# SCH_MUSICA_2024-05-24.net
KiCad netlist of a schematic drawn in EasyEDA
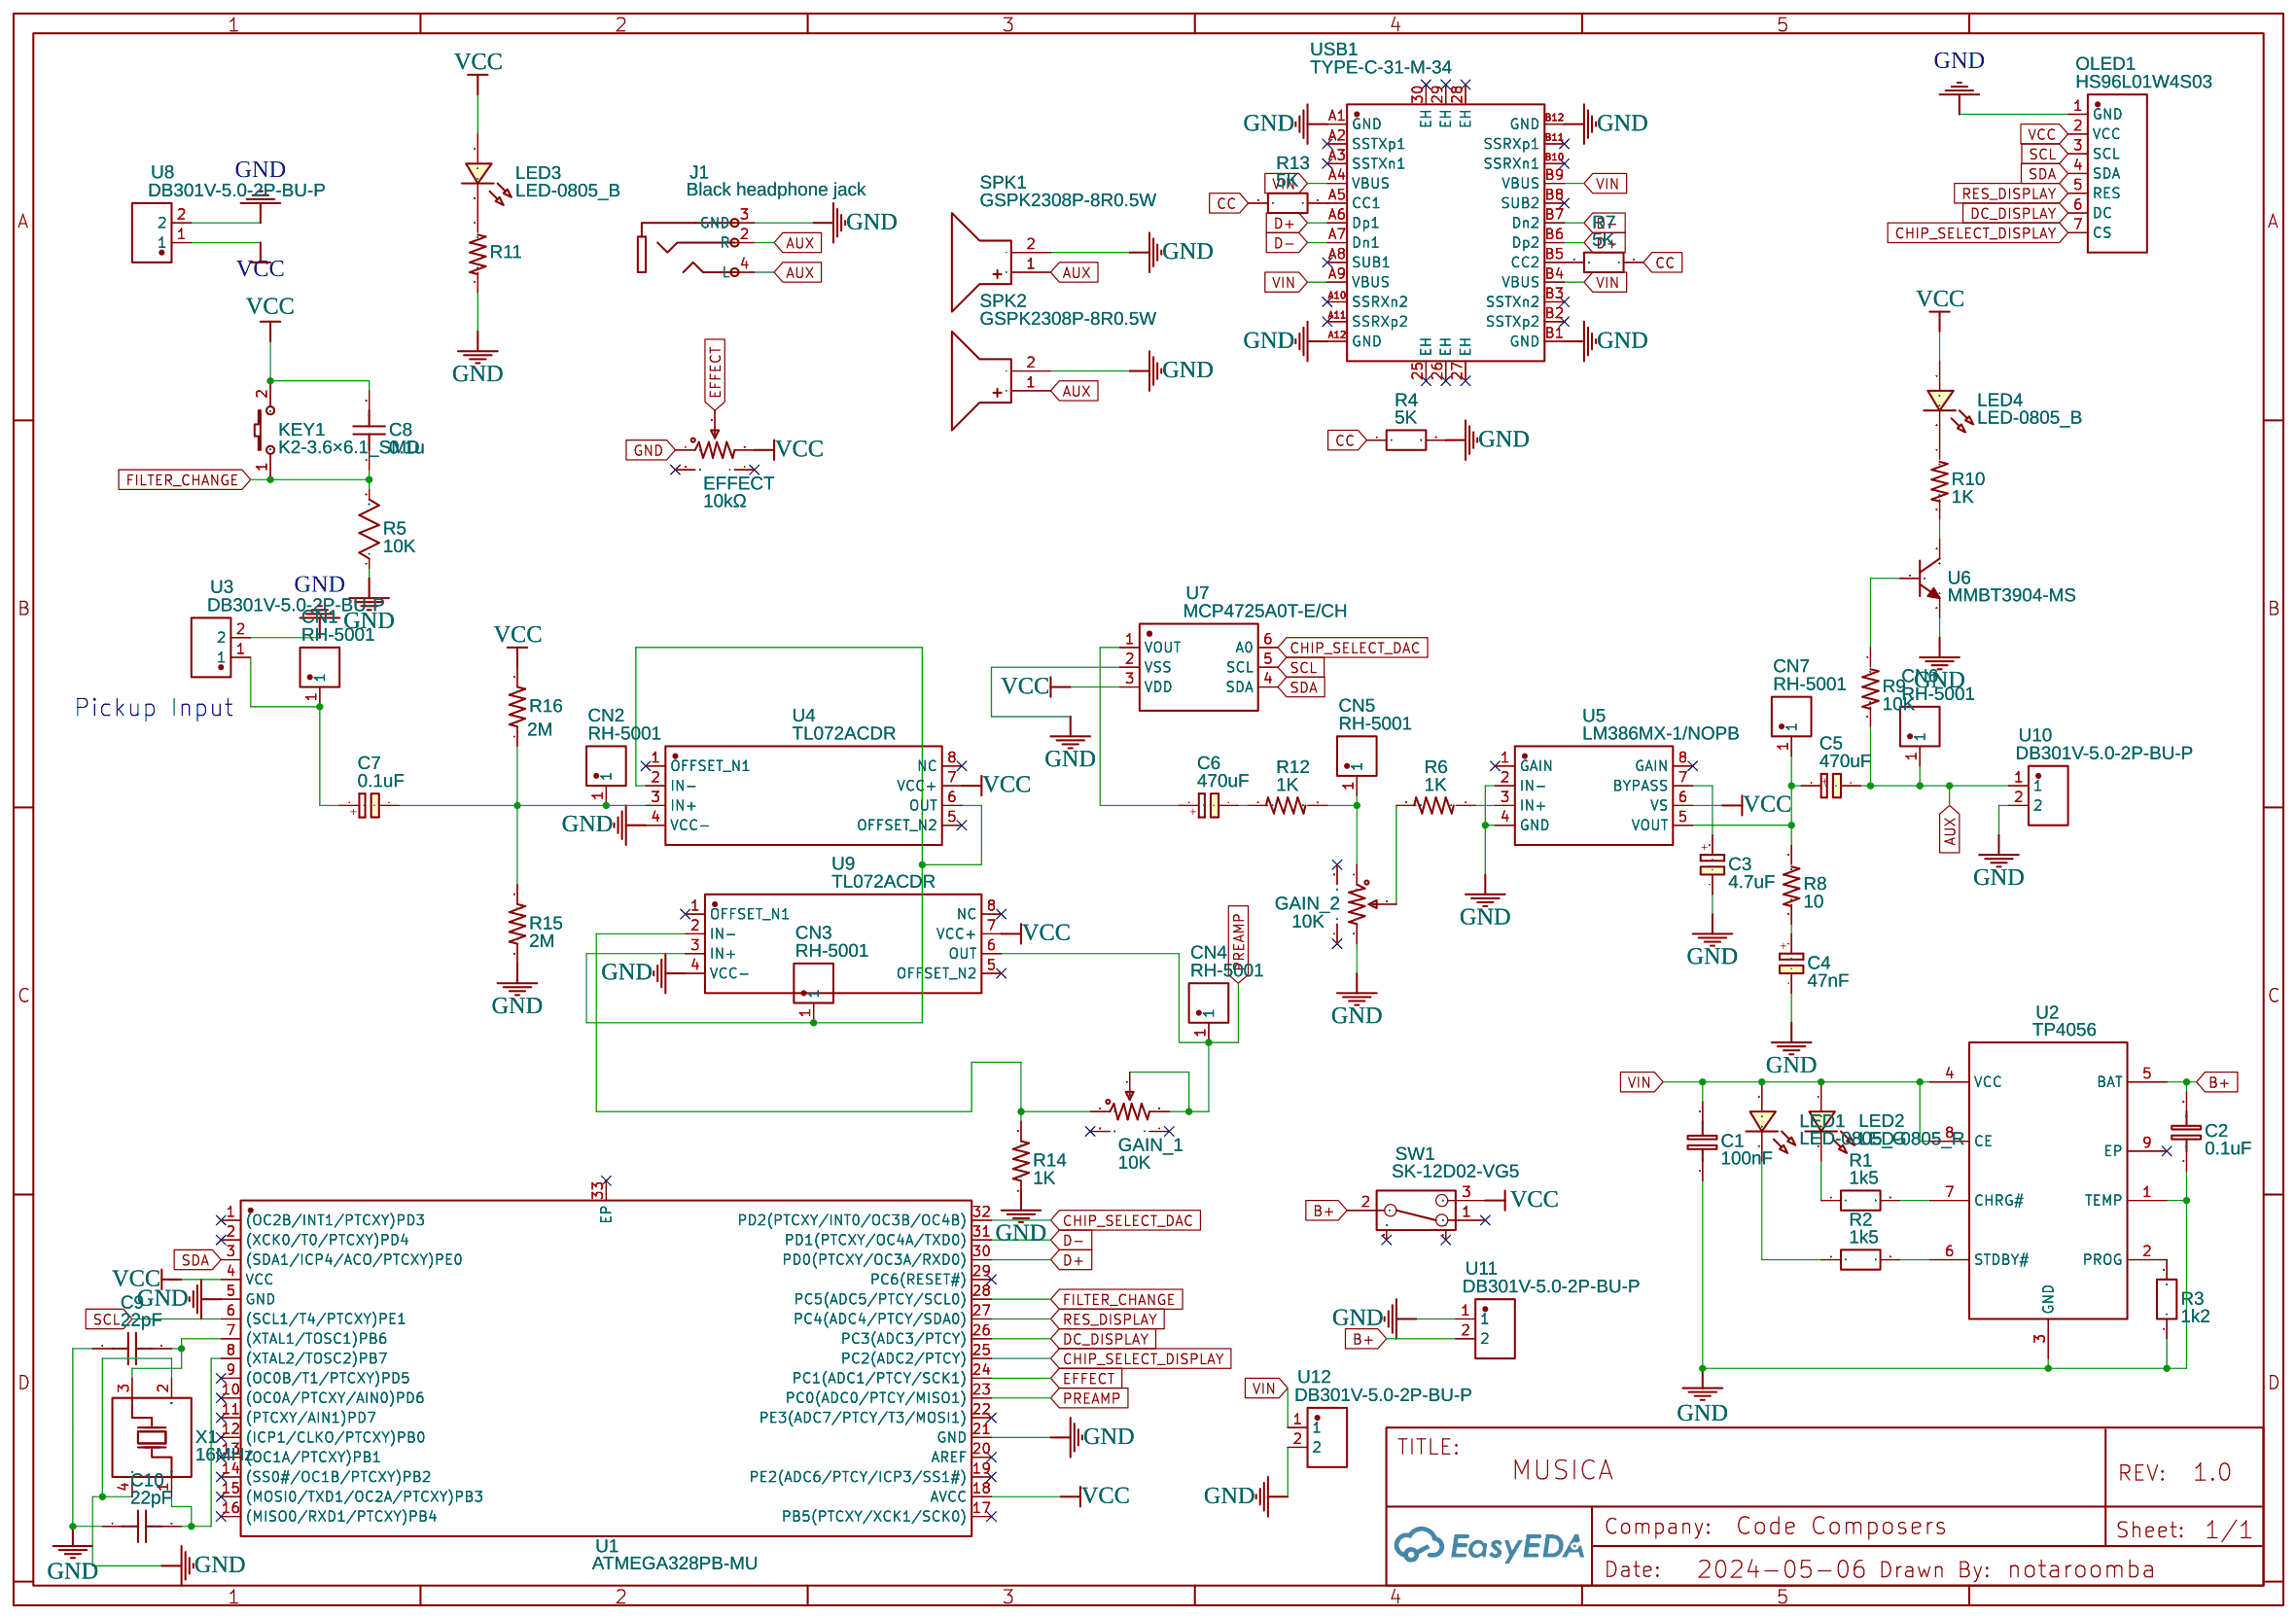
[diagram p0: schematic sheet]

(export (version "E")
  (design (tool "Eeschema 10.0.6"))
  (components
    (comp (ref "C1") (value "100nF") (libsource (lib "") (part "C_0603_EU")))
    (comp (ref "C2") (value "0.1uF") (libsource (lib "") (part "C_0603_EU")))
    (comp (ref "C3") (value "4.7uF") (libsource (lib "") (part "CAPACITOR_POL_S_2")))
    (comp (ref "C4") (value "47nF") (libsource (lib "") (part "CAPACITOR_POL_S_2")))
    (comp (ref "C5") (value "470uF") (libsource (lib "") (part "CAPACITOR_POL_S")))
    (comp (ref "C6") (value "470uF") (libsource (lib "") (part "CAPACITOR_POL_S_1")))
    (comp (ref "C7") (value "0.1uF") (libsource (lib "") (part "CAPACITOR_POL_S_1")))
    (comp (ref "C8") (value "0.1u") (libsource (lib "") (part "C_0603_US")))
    (comp (ref "C9") (value "22pF") (libsource (lib "") (part "C_0603_US_1")))
    (comp (ref "C10") (value "22pF") (libsource (lib "") (part "C_0603_US_1")))
    (comp (ref "CN1")
      (value "RH-5001")
      (fields (field (name "Manufacturer") "荣和"))
      (libsource (lib "") (part "RH-5001"))
    )
    (comp (ref "CN2")
      (value "RH-5001")
      (fields (field (name "Manufacturer") "荣和"))
      (libsource (lib "") (part "RH-5001"))
    )
    (comp (ref "CN3")
      (value "RH-5001")
      (fields (field (name "Manufacturer") "荣和"))
      (libsource (lib "") (part "RH-5001"))
    )
    (comp (ref "CN4")
      (value "RH-5001")
      (fields (field (name "Manufacturer") "荣和"))
      (libsource (lib "") (part "RH-5001"))
    )
    (comp (ref "CN5")
      (value "RH-5001")
      (fields (field (name "Manufacturer") "荣和"))
      (libsource (lib "") (part "RH-5001"))
    )
    (comp (ref "CN6")
      (value "RH-5001")
      (fields (field (name "Manufacturer") "荣和"))
      (libsource (lib "") (part "RH-5001"))
    )
    (comp (ref "CN7")
      (value "RH-5001")
      (fields (field (name "Manufacturer") "荣和"))
      (libsource (lib "") (part "RH-5001"))
    )
    (comp (ref "EFFECT")
      (value "10kΩ")
      (fields
        (field (name "Manufacturer Part") "RK09L114001T")
        (field (name "Manufacturer") "ALPSALPINE(阿尔卑斯阿尔派)")
      )
      (libsource (lib "") (part "RK09L114001T_1"))
    )
    (comp (ref "GAIN_1")
      (value "10K")
      (fields
        (field (name "Manufacturer Part") "RK09L114001T")
        (field (name "Manufacturer") "ALPSALPINE(阿尔卑斯阿尔派)")
      )
      (libsource (lib "") (part "RK09L114001T_2"))
    )
    (comp (ref "GAIN_2")
      (value "10K")
      (fields
        (field (name "Manufacturer Part") "RK09L114001T")
        (field (name "Manufacturer") "ALPSALPINE(阿尔卑斯阿尔派)")
      )
      (libsource (lib "") (part "RK09L114001T"))
    )
    (comp (ref "J1")
      (value "Black headphone jack")
      (fields (field (name "Manufacturer Part") "320B直插") (field (name "Manufacturer") "BOOMELE(博穆精密)"))
      (libsource (lib "") (part "Black headphone jack"))
    )
    (comp (ref "KEY1")
      (value "K2-3.6×6.1_SMD")
      (fields (field (name "Manufacturer Part") "K2-1107ST-A4SW-06"))
      (libsource (lib "") (part "K2-3.6×6.1_SMD"))
    )
    (comp (ref "LED1")
      (value "LED-0805_G")
      (fields (field (name "Manufacturer Part") "NCD0805G1") (field (name "Manufacturer") "国星光电"))
      (libsource (lib "") (part "LED-0805_G"))
    )
    (comp (ref "LED2")
      (value "LED-0805_R")
      (fields
        (field (name "Manufacturer Part") "17-21SURC/S530-A3/TR8")
        (field (name "Manufacturer") "EVERLIGHT(台湾亿光)")
      )
      (libsource (lib "") (part "LED-0805_R"))
    )
    (comp (ref "LED3")
      (value "LED-0805_B")
      (fields (field (name "Manufacturer Part") "D-B080508B1-KS2") (field (name "Manufacturer") "方舟 ARKLED"))
      (libsource (lib "") (part "LED-0805_B"))
    )
    (comp (ref "LED4")
      (value "LED-0805_B")
      (fields (field (name "Manufacturer Part") "D-B080508B1-KS2") (field (name "Manufacturer") "方舟 ARKLED"))
      (libsource (lib "") (part "LED-0805_B"))
    )
    (comp (ref "OLED1")
      (value "HS96L01W4S03")
      (fields (field (name "Manufacturer") "HS(汉昇)"))
      (libsource (lib "") (part "HS96L01W4S03"))
    )
    (comp (ref "R1") (value "1k5") (libsource (lib "") (part "R_0603_EU")))
    (comp (ref "R2") (value "1k5") (libsource (lib "") (part "R_0603_EU")))
    (comp (ref "R3") (value "1k2") (libsource (lib "") (part "R_0603_EU_1")))
    (comp (ref "R4") (value "5K") (libsource (lib "") (part "R_0603_EU")))
    (comp (ref "R5") (value "10K") (libsource (lib "") (part "R_0603_US")))
    (comp (ref "R6") (value "1K") (libsource (lib "") (part "RESISTOR0805-RES_1")))
    (comp (ref "R7") (value "5K") (libsource (lib "") (part "R_0603_EU")))
    (comp (ref "R8") (value "10") (libsource (lib "") (part "RESISTOR0805-RES_2")))
    (comp (ref "R9") (value "10K") (libsource (lib "") (part "RESISTOR0805-RES_2")))
    (comp (ref "R10") (value "1K") (libsource (lib "") (part "RESISTOR0805-RES_2")))
    (comp (ref "R11") (value "1K") (libsource (lib "") (part "RESISTOR0805-RES_2")))
    (comp (ref "R12") (value "1K") (libsource (lib "") (part "RESISTOR0805-RES_1")))
    (comp (ref "R13") (value "5K") (libsource (lib "") (part "R_0603_EU")))
    (comp (ref "R14") (value "1K") (libsource (lib "") (part "RESISTOR0805-RES")))
    (comp (ref "R15") (value "2M") (libsource (lib "") (part "RESISTOR0805-RES")))
    (comp (ref "R16") (value "2M") (libsource (lib "") (part "RESISTOR0805-RES")))
    (comp (ref "SPK1")
      (value "GSPK2308P-8R0.5W")
      (fields (field (name "Manufacturer") "INGHAi(赢海)"))
      (libsource (lib "") (part "GSPK2308P-8R0.5W"))
    )
    (comp (ref "SPK2")
      (value "GSPK2308P-8R0.5W")
      (fields (field (name "Manufacturer") "INGHAi(赢海)"))
      (libsource (lib "") (part "GSPK2308P-8R0.5W"))
    )
    (comp (ref "SW1")
      (value "SK-12D02-VG5")
      (fields (field (name "Manufacturer") "Rectangular Connectors - Contacts"))
      (libsource (lib "") (part "SK-12D02-VG5"))
    )
    (comp (ref "U1")
      (value "ATMEGA328PB-MU")
      (fields (field (name "Manufacturer") "MICROCHIP(美国微芯)"))
      (libsource (lib "") (part "ATMEGA328PB-MU"))
    )
    (comp (ref "U2")
      (value "TP4056")
      (fields
        (field (name "Manufacturer Part") "TP4056-42-ESOP8")
        (field (name "Manufacturer") "TOPPOWER(南京拓微)")
      )
      (libsource (lib "") (part "TP4056"))
    )
    (comp (ref "U3")
      (value "DB301V-5.0-2P-BU-P")
      (fields (field (name "Manufacturer") "DORABO(地博电气)"))
      (libsource (lib "") (part "DB301V-5.0-2P-BU-P_1"))
    )
    (comp (ref "U4")
      (value "TL072ACDR")
      (fields (field (name "Manufacturer") "TI(德州仪器)"))
      (libsource (lib "") (part "TL072ACDR"))
    )
    (comp (ref "U5")
      (value "LM386MX-1/NOPB")
      (fields (field (name "Manufacturer") "TI(德州仪器)"))
      (libsource (lib "") (part "LM386MX-1/NOPB"))
    )
    (comp (ref "U6")
      (value "MMBT3904-MS")
      (fields (field (name "Manufacturer") "MSKSEMI(美森科)"))
      (libsource (lib "") (part "MMBT3904-MS"))
    )
    (comp (ref "U7")
      (value "MCP4725A0T-E/CH")
      (fields (field (name "Manufacturer") "MICROCHIP(美国微芯)"))
      (libsource (lib "") (part "MCP4725A0T-E/CH"))
    )
    (comp (ref "U8")
      (value "DB301V-5.0-2P-BU-P")
      (fields (field (name "Manufacturer") "DORABO(地博电气)"))
      (libsource (lib "") (part "DB301V-5.0-2P-BU-P_1"))
    )
    (comp (ref "U9")
      (value "TL072ACDR")
      (fields (field (name "Manufacturer") "TI(德州仪器)"))
      (libsource (lib "") (part "TL072ACDR"))
    )
    (comp (ref "U10")
      (value "DB301V-5.0-2P-BU-P")
      (fields (field (name "Manufacturer") "DORABO(地博电气)"))
      (libsource (lib "") (part "DB301V-5.0-2P-BU-P"))
    )
    (comp (ref "U11")
      (value "DB301V-5.0-2P-BU-P")
      (fields (field (name "Manufacturer") "DORABO(地博电气)"))
      (libsource (lib "") (part "DB301V-5.0-2P-BU-P"))
    )
    (comp (ref "U12")
      (value "DB301V-5.0-2P-BU-P")
      (fields (field (name "Manufacturer") "DORABO(地博电气)"))
      (libsource (lib "") (part "DB301V-5.0-2P-BU-P"))
    )
    (comp (ref "USB1")
      (value "TYPE-C-31-M-34")
      (fields (field (name "Manufacturer") "韩国韩荣"))
      (libsource (lib "") (part "TYPE-C-31-M-34"))
    )
    (comp (ref "X1")
      (value "16MHz")
      (fields (field (name "Manufacturer Part") "X322516MLB4SI") (field (name "Manufacturer") "YXC(扬兴晶振)"))
      (libsource (lib "") (part "X322516MLB4SI"))
    )
  )
  (nets
    (net (code "1") (name "AUX") (class "Default")
      (node (ref "C5") (pin "-") (pinfunction "-_-") (pintype "unspecified"))
      (node (ref "CN6") (pin "1") (pinfunction "1_1") (pintype "unspecified"))
      (node (ref "J1") (pin "2") (pinfunction "R_2") (pintype "input"))
      (node (ref "J1") (pin "4") (pinfunction "L_4") (pintype "input"))
      (node (ref "R9") (pin "2") (pinfunction "2_2") (pintype "bidirectional"))
      (node (ref "SPK1") (pin "1") (pinfunction "+_1") (pintype "unspecified"))
      (node (ref "SPK2") (pin "1") (pinfunction "+_1") (pintype "unspecified"))
      (node (ref "U10") (pin "1") (pinfunction "1_1") (pintype "unspecified"))
    )
    (net (code "2") (name "B+") (class "Default")
      (node (ref "C2") (pin "2") (pinfunction "2_2") (pintype "unspecified"))
      (node (ref "SW1") (pin "2") (pinfunction "2_2") (pintype "unspecified"))
      (node (ref "U11") (pin "2") (pinfunction "2_2") (pintype "unspecified"))
      (node (ref "U2") (pin "5") (pinfunction "BAT_5") (pintype "unspecified"))
    )
    (net (code "3") (name "CC") (class "Default")
      (node (ref "R13") (pin "1") (pinfunction "1_1") (pintype "unspecified"))
      (node (ref "R4") (pin "1") (pinfunction "1_1") (pintype "unspecified"))
      (node (ref "R7") (pin "2") (pinfunction "2_2") (pintype "unspecified"))
    )
    (net (code "4") (name "CHIP_SELECT_DAC") (class "Default")
      (node (ref "U1") (pin "32") (pinfunction "PD2(PTCXY/INT0/OC3B/OC4B)_32") (pintype "unspecified"))
      (node (ref "U7") (pin "6") (pinfunction "A0_6") (pintype "unspecified"))
    )
    (net (code "5") (name "CHIP_SELECT_DISPLAY") (class "Default")
      (node (ref "OLED1") (pin "7") (pinfunction "CS_7") (pintype "unspecified"))
      (node (ref "U1") (pin "25") (pinfunction "PC2(ADC2/PTCY)_25") (pintype "unspecified"))
    )
    (net (code "6") (name "D+") (class "Default")
      (node (ref "U1") (pin "30") (pinfunction "PD0(PTCXY/OC3A/RXD0)_30") (pintype "unspecified"))
      (node (ref "USB1") (pin "A6") (pinfunction "Dp1_A6") (pintype "unspecified"))
      (node (ref "USB1") (pin "B6") (pinfunction "Dp2_B6") (pintype "unspecified"))
    )
    (net (code "7") (name "D-") (class "Default")
      (node (ref "U1") (pin "31") (pinfunction "PD1(PTCXY/OC4A/TXD0)_31") (pintype "unspecified"))
      (node (ref "USB1") (pin "A7") (pinfunction "Dn1_A7") (pintype "unspecified"))
      (node (ref "USB1") (pin "B7") (pinfunction "Dn2_B7") (pintype "unspecified"))
    )
    (net (code "8") (name "DC_DISPLAY") (class "Default")
      (node (ref "OLED1") (pin "6") (pinfunction "DC_6") (pintype "unspecified"))
      (node (ref "U1") (pin "26") (pinfunction "PC3(ADC3/PTCY)_26") (pintype "unspecified"))
    )
    (net (code "9") (name "EFFECT") (class "Default")
      (node (ref "EFFECT") (pin "2") (pinfunction "2_2") (pintype "unspecified"))
      (node (ref "U1") (pin "24") (pinfunction "PC1(ADC1/PTCY/SCK1)_24") (pintype "unspecified"))
    )
    (net (code "10") (name "FILTER_CHANGE") (class "Default")
      (node (ref "C8") (pin "1") (pinfunction "1_1") (pintype "unspecified"))
      (node (ref "KEY1") (pin "1") (pinfunction "1_1") (pintype "unspecified"))
      (node (ref "R5") (pin "2") (pinfunction "2_2") (pintype "unspecified"))
      (node (ref "U1") (pin "28") (pinfunction "PC5(ADC5/PTCY/SCL0)_28") (pintype "unspecified"))
    )
    (net (code "11") (name "GND") (class "Default")
      (node (ref "C1") (pin "1") (pinfunction "1_1") (pintype "unspecified"))
      (node (ref "C10") (pin "1") (pinfunction "1_1") (pintype "unspecified"))
      (node (ref "C2") (pin "1") (pinfunction "1_1") (pintype "unspecified"))
      (node (ref "C3") (pin "-") (pinfunction "-_-") (pintype "unspecified"))
      (node (ref "C4") (pin "-") (pinfunction "-_-") (pintype "unspecified"))
      (node (ref "C9") (pin "1") (pinfunction "1_1") (pintype "unspecified"))
      (node (ref "EFFECT") (pin "1") (pinfunction "1_1") (pintype "unspecified"))
      (node (ref "GAIN_2") (pin "3") (pinfunction "3_3") (pintype "unspecified"))
      (node (ref "J1") (pin "3") (pinfunction "GND_3") (pintype "input"))
      (node (ref "OLED1") (pin "1") (pinfunction "GND_1") (pintype "unspecified"))
      (node (ref "R11") (pin "2") (pinfunction "2_2") (pintype "bidirectional"))
      (node (ref "R14") (pin "1") (pinfunction "1_1") (pintype "bidirectional"))
      (node (ref "R15") (pin "1") (pinfunction "1_1") (pintype "bidirectional"))
      (node (ref "R3") (pin "1") (pinfunction "1_1") (pintype "unspecified"))
      (node (ref "R4") (pin "2") (pinfunction "2_2") (pintype "unspecified"))
      (node (ref "R5") (pin "1") (pinfunction "1_1") (pintype "unspecified"))
      (node (ref "SPK1") (pin "2") (pinfunction "-_2") (pintype "unspecified"))
      (node (ref "SPK2") (pin "2") (pinfunction "-_2") (pintype "unspecified"))
      (node (ref "U1") (pin "21") (pinfunction "GND_21") (pintype "unspecified"))
      (node (ref "U1") (pin "5") (pinfunction "GND_5") (pintype "unspecified"))
      (node (ref "U10") (pin "2") (pinfunction "2_2") (pintype "unspecified"))
      (node (ref "U11") (pin "1") (pinfunction "1_1") (pintype "unspecified"))
      (node (ref "U12") (pin "2") (pinfunction "2_2") (pintype "unspecified"))
      (node (ref "U2") (pin "1") (pinfunction "TEMP_1") (pintype "unspecified"))
      (node (ref "U2") (pin "3") (pinfunction "GND_3") (pintype "unspecified"))
      (node (ref "U3") (pin "2") (pinfunction "2_2") (pintype "unspecified"))
      (node (ref "U4") (pin "4") (pinfunction "VCC-_4") (pintype "unspecified"))
      (node (ref "U5") (pin "2") (pinfunction "IN-_2") (pintype "unspecified"))
      (node (ref "U5") (pin "4") (pinfunction "GND_4") (pintype "unspecified"))
      (node (ref "U6") (pin "2") (pinfunction "E_2") (pintype "input"))
      (node (ref "U7") (pin "2") (pinfunction "VSS_2") (pintype "unspecified"))
      (node (ref "U8") (pin "2") (pinfunction "2_2") (pintype "unspecified"))
      (node (ref "U9") (pin "4") (pinfunction "VCC-_4") (pintype "unspecified"))
      (node (ref "USB1") (pin "A1") (pinfunction "GND_A1") (pintype "unspecified"))
      (node (ref "USB1") (pin "A12") (pinfunction "GND_A12") (pintype "unspecified"))
      (node (ref "USB1") (pin "B1") (pinfunction "GND_B1") (pintype "unspecified"))
      (node (ref "USB1") (pin "B12") (pinfunction "GND_B12") (pintype "unspecified"))
      (node (ref "X1") (pin "2") (pinfunction "GND_2") (pintype "unspecified"))
      (node (ref "X1") (pin "4") (pinfunction "GND_4") (pintype "unspecified"))
    )
    (net (code "12") (name "Net-(C4-Pad+)") (class "Default")
      (node (ref "C4") (pin "+") (pinfunction "+_+") (pintype "unspecified"))
      (node (ref "R8") (pin "2") (pinfunction "2_2") (pintype "bidirectional"))
    )
    (net (code "13") (name "Net-(C6-Pad-)") (class "Default")
      (node (ref "C6") (pin "-") (pinfunction "-_-") (pintype "unspecified"))
      (node (ref "R12") (pin "2") (pinfunction "2_2") (pintype "bidirectional"))
    )
    (net (code "14") (name "Net-(C7-Pad+)") (class "Default")
      (node (ref "C7") (pin "+") (pinfunction "+_+") (pintype "unspecified"))
      (node (ref "CN1") (pin "1") (pinfunction "1_1") (pintype "unspecified"))
      (node (ref "U3") (pin "1") (pinfunction "1_1") (pintype "unspecified"))
    )
    (net (code "15") (name "Net-(CN5-Pad1)") (class "Default")
      (node (ref "CN5") (pin "1") (pinfunction "1_1") (pintype "unspecified"))
      (node (ref "GAIN_2") (pin "1") (pinfunction "1_1") (pintype "unspecified"))
      (node (ref "R12") (pin "1") (pinfunction "1_1") (pintype "bidirectional"))
    )
    (net (code "16") (name "Net-(GAIN_2-Pad2)") (class "Default")
      (node (ref "GAIN_2") (pin "2") (pinfunction "2_2") (pintype "unspecified"))
      (node (ref "R6") (pin "2") (pinfunction "2_2") (pintype "bidirectional"))
    )
    (net (code "17") (name "Net-(LED1-Pad2)") (class "Default")
      (node (ref "LED1") (pin "2") (pinfunction "2_2") (pintype "unspecified"))
      (node (ref "R2") (pin "1") (pinfunction "1_1") (pintype "unspecified"))
    )
    (net (code "18") (name "Net-(LED2-Pad2)") (class "Default")
      (node (ref "LED2") (pin "2") (pinfunction "2_2") (pintype "unspecified"))
      (node (ref "R1") (pin "1") (pinfunction "1_1") (pintype "unspecified"))
    )
    (net (code "19") (name "Net-(LED3-Pad2)") (class "Default")
      (node (ref "LED3") (pin "2") (pinfunction "2_2") (pintype "unspecified"))
      (node (ref "R11") (pin "1") (pinfunction "1_1") (pintype "bidirectional"))
    )
    (net (code "20") (name "Net-(LED4-Pad2)") (class "Default")
      (node (ref "LED4") (pin "2") (pinfunction "2_2") (pintype "unspecified"))
      (node (ref "R10") (pin "1") (pinfunction "1_1") (pintype "bidirectional"))
    )
    (net (code "21") (name "Net-(U1-(XTAL1{slash}TOSC1)PB6)") (class "Default")
      (node (ref "C9") (pin "2") (pinfunction "2_2") (pintype "unspecified"))
      (node (ref "U1") (pin "7") (pinfunction "(XTAL1/TOSC1)PB6_7") (pintype "unspecified"))
      (node (ref "X1") (pin "3") (pinfunction "OSC2_3") (pintype "unspecified"))
    )
    (net (code "22") (name "Net-(U1-(XTAL2{slash}TOSC2)PB7)") (class "Default")
      (node (ref "C10") (pin "2") (pinfunction "2_2") (pintype "unspecified"))
      (node (ref "U1") (pin "8") (pinfunction "(XTAL2/TOSC2)PB7_8") (pintype "unspecified"))
      (node (ref "X1") (pin "1") (pinfunction "OSC1_1") (pintype "unspecified"))
    )
    (net (code "23") (name "Net-(U2-CHRG#)") (class "Default")
      (node (ref "R1") (pin "2") (pinfunction "2_2") (pintype "unspecified"))
      (node (ref "U2") (pin "7") (pinfunction "CHRG#_7") (pintype "unspecified"))
    )
    (net (code "24") (name "Net-(U2-PROG)") (class "Default")
      (node (ref "R3") (pin "2") (pinfunction "2_2") (pintype "unspecified"))
      (node (ref "U2") (pin "2") (pinfunction "PROG_2") (pintype "unspecified"))
    )
    (net (code "25") (name "Net-(U2-STDBY#)") (class "Default")
      (node (ref "R2") (pin "2") (pinfunction "2_2") (pintype "unspecified"))
      (node (ref "U2") (pin "6") (pinfunction "STDBY#_6") (pintype "unspecified"))
    )
    (net (code "26") (name "Net-(U4-IN+)") (class "Default")
      (node (ref "C7") (pin "-") (pinfunction "-_-") (pintype "unspecified"))
      (node (ref "CN2") (pin "1") (pinfunction "1_1") (pintype "unspecified"))
      (node (ref "R15") (pin "2") (pinfunction "2_2") (pintype "bidirectional"))
      (node (ref "R16") (pin "1") (pinfunction "1_1") (pintype "bidirectional"))
      (node (ref "U4") (pin "3") (pinfunction "IN+_3") (pintype "unspecified"))
    )
    (net (code "27") (name "Net-(U4-IN-)") (class "Default")
      (node (ref "CN3") (pin "1") (pinfunction "1_1") (pintype "unspecified"))
      (node (ref "U4") (pin "2") (pinfunction "IN-_2") (pintype "unspecified"))
      (node (ref "U4") (pin "6") (pinfunction "OUT_6") (pintype "unspecified"))
      (node (ref "U9") (pin "3") (pinfunction "IN+_3") (pintype "unspecified"))
    )
    (net (code "28") (name "Net-(U5-BYPASS)") (class "Default")
      (node (ref "C3") (pin "+") (pinfunction "+_+") (pintype "unspecified"))
      (node (ref "U5") (pin "7") (pinfunction "BYPASS_7") (pintype "unspecified"))
    )
    (net (code "29") (name "Net-(U5-IN+)") (class "Default")
      (node (ref "R6") (pin "1") (pinfunction "1_1") (pintype "bidirectional"))
      (node (ref "U5") (pin "3") (pinfunction "IN+_3") (pintype "unspecified"))
    )
    (net (code "30") (name "Net-(U5-VOUT)") (class "Default")
      (node (ref "C5") (pin "+") (pinfunction "+_+") (pintype "unspecified"))
      (node (ref "CN7") (pin "1") (pinfunction "1_1") (pintype "unspecified"))
      (node (ref "R8") (pin "1") (pinfunction "1_1") (pintype "bidirectional"))
      (node (ref "U5") (pin "5") (pinfunction "VOUT_5") (pintype "unspecified"))
    )
    (net (code "31") (name "Net-(U6-B)") (class "Default")
      (node (ref "R9") (pin "1") (pinfunction "1_1") (pintype "bidirectional"))
      (node (ref "U6") (pin "1") (pinfunction "B_1") (pintype "input"))
    )
    (net (code "32") (name "Net-(U6-C)") (class "Default")
      (node (ref "R10") (pin "2") (pinfunction "2_2") (pintype "bidirectional"))
      (node (ref "U6") (pin "3") (pinfunction "C_3") (pintype "input"))
    )
    (net (code "33") (name "Net-(U7-VOUT)") (class "Default")
      (node (ref "C6") (pin "+") (pinfunction "+_+") (pintype "unspecified"))
      (node (ref "U7") (pin "1") (pinfunction "VOUT_1") (pintype "unspecified"))
    )
    (net (code "34") (name "Net-(U9-IN-)") (class "Default")
      (node (ref "GAIN_1") (pin "1") (pinfunction "1_1") (pintype "unspecified"))
      (node (ref "R14") (pin "2") (pinfunction "2_2") (pintype "bidirectional"))
      (node (ref "U9") (pin "2") (pinfunction "IN-_2") (pintype "unspecified"))
    )
    (net (code "35") (name "Net-(USB1-CC1)") (class "Default")
      (node (ref "R13") (pin "2") (pinfunction "2_2") (pintype "unspecified"))
      (node (ref "USB1") (pin "A5") (pinfunction "CC1_A5") (pintype "unspecified"))
    )
    (net (code "36") (name "Net-(USB1-CC2)") (class "Default")
      (node (ref "R7") (pin "1") (pinfunction "1_1") (pintype "unspecified"))
      (node (ref "USB1") (pin "B5") (pinfunction "CC2_B5") (pintype "unspecified"))
    )
    (net (code "37") (name "PREAMP") (class "Default")
      (node (ref "CN4") (pin "1") (pinfunction "1_1") (pintype "unspecified"))
      (node (ref "GAIN_1") (pin "2") (pinfunction "2_2") (pintype "unspecified"))
      (node (ref "GAIN_1") (pin "3") (pinfunction "3_3") (pintype "unspecified"))
      (node (ref "U1") (pin "23") (pinfunction "PC0(ADC0/PTCY/MISO1)_23") (pintype "unspecified"))
      (node (ref "U9") (pin "6") (pinfunction "OUT_6") (pintype "unspecified"))
    )
    (net (code "38") (name "RES_DISPLAY") (class "Default")
      (node (ref "OLED1") (pin "5") (pinfunction "RES_5") (pintype "unspecified"))
      (node (ref "U1") (pin "27") (pinfunction "PC4(ADC4/PTCY/SDA0)_27") (pintype "unspecified"))
    )
    (net (code "39") (name "SCL") (class "Default")
      (node (ref "OLED1") (pin "3") (pinfunction "SCL_3") (pintype "unspecified"))
      (node (ref "U1") (pin "6") (pinfunction "(SCL1/T4/PTCXY)PE1_6") (pintype "unspecified"))
      (node (ref "U7") (pin "5") (pinfunction "SCL_5") (pintype "unspecified"))
    )
    (net (code "40") (name "SDA") (class "Default")
      (node (ref "OLED1") (pin "4") (pinfunction "SDA_4") (pintype "unspecified"))
      (node (ref "U1") (pin "3") (pinfunction "(SDA1/ICP4/ACO/PTCXY)PE0_3") (pintype "unspecified"))
      (node (ref "U7") (pin "4") (pinfunction "SDA_4") (pintype "unspecified"))
    )
    (net (code "41") (name "VCC") (class "Default")
      (node (ref "C8") (pin "2") (pinfunction "2_2") (pintype "unspecified"))
      (node (ref "EFFECT") (pin "3") (pinfunction "3_3") (pintype "unspecified"))
      (node (ref "KEY1") (pin "2") (pinfunction "2_2") (pintype "unspecified"))
      (node (ref "LED3") (pin "1") (pinfunction "1_1") (pintype "unspecified"))
      (node (ref "LED4") (pin "1") (pinfunction "1_1") (pintype "unspecified"))
      (node (ref "OLED1") (pin "2") (pinfunction "VCC_2") (pintype "unspecified"))
      (node (ref "R16") (pin "2") (pinfunction "2_2") (pintype "bidirectional"))
      (node (ref "SW1") (pin "3") (pinfunction "3_3") (pintype "unspecified"))
      (node (ref "U1") (pin "18") (pinfunction "AVCC_18") (pintype "unspecified"))
      (node (ref "U1") (pin "4") (pinfunction "VCC_4") (pintype "unspecified"))
      (node (ref "U4") (pin "7") (pinfunction "VCC+_7") (pintype "unspecified"))
      (node (ref "U5") (pin "6") (pinfunction "VS_6") (pintype "unspecified"))
      (node (ref "U7") (pin "3") (pinfunction "VDD_3") (pintype "unspecified"))
      (node (ref "U8") (pin "1") (pinfunction "1_1") (pintype "unspecified"))
      (node (ref "U9") (pin "7") (pinfunction "VCC+_7") (pintype "unspecified"))
    )
    (net (code "42") (name "VIN") (class "Default")
      (node (ref "C1") (pin "2") (pinfunction "2_2") (pintype "unspecified"))
      (node (ref "LED1") (pin "1") (pinfunction "1_1") (pintype "unspecified"))
      (node (ref "LED2") (pin "1") (pinfunction "1_1") (pintype "unspecified"))
      (node (ref "U12") (pin "1") (pinfunction "1_1") (pintype "unspecified"))
      (node (ref "U2") (pin "4") (pinfunction "VCC_4") (pintype "unspecified"))
      (node (ref "U2") (pin "8") (pinfunction "CE_8") (pintype "unspecified"))
      (node (ref "USB1") (pin "A4") (pinfunction "VBUS_A4") (pintype "unspecified"))
      (node (ref "USB1") (pin "A9") (pinfunction "VBUS_A9") (pintype "unspecified"))
      (node (ref "USB1") (pin "B4") (pinfunction "VBUS_B4") (pintype "unspecified"))
      (node (ref "USB1") (pin "B9") (pinfunction "VBUS_B9") (pintype "unspecified"))
    )
    (net (code "43") (name "unconnected-(EFFECT-Pad4)") (class "Default")
      (node (ref "EFFECT") (pin "4") (pinfunction "4_4") (pintype "unspecified+no_connect"))
    )
    (net (code "44") (name "unconnected-(EFFECT-Pad5)") (class "Default")
      (node (ref "EFFECT") (pin "5") (pinfunction "5_5") (pintype "unspecified+no_connect"))
    )
    (net (code "45") (name "unconnected-(GAIN_1-Pad4)") (class "Default")
      (node (ref "GAIN_1") (pin "4") (pinfunction "4_4") (pintype "unspecified+no_connect"))
    )
    (net (code "46") (name "unconnected-(GAIN_1-Pad5)") (class "Default")
      (node (ref "GAIN_1") (pin "5") (pinfunction "5_5") (pintype "unspecified+no_connect"))
    )
    (net (code "47") (name "unconnected-(GAIN_2-Pad4)") (class "Default")
      (node (ref "GAIN_2") (pin "4") (pinfunction "4_4") (pintype "unspecified+no_connect"))
    )
    (net (code "48") (name "unconnected-(GAIN_2-Pad5)") (class "Default")
      (node (ref "GAIN_2") (pin "5") (pinfunction "5_5") (pintype "unspecified+no_connect"))
    )
    (net (code "49") (name "unconnected-(SW1-Pad1)") (class "Default")
      (node (ref "SW1") (pin "1") (pinfunction "1_1") (pintype "unspecified+no_connect"))
    )
    (net (code "50") (name "unconnected-(SW1-Pad4)") (class "Default")
      (node (ref "SW1") (pin "4") (pinfunction "4_4") (pintype "unspecified+no_connect"))
    )
    (net (code "51") (name "unconnected-(SW1-Pad5)") (class "Default")
      (node (ref "SW1") (pin "5") (pinfunction "5_5") (pintype "unspecified+no_connect"))
    )
    (net (code "52") (name "unconnected-(U1-(ICP1{slash}CLKO{slash}PTCXY)PB0-Pad12)") (class "Default")
      (node (ref "U1") (pin "12") (pinfunction "(ICP1/CLKO/PTCXY)PB0_12") (pintype "unspecified+no_connect"))
    )
    (net (code "53") (name "unconnected-(U1-(MISO0{slash}RXD1{slash}PTCXY)PB4-Pad16)") (class "Default")
      (node (ref "U1") (pin "16") (pinfunction "(MISO0/RXD1/PTCXY)PB4_16") (pintype "unspecified+no_connect"))
    )
    (net (code "54") (name "unconnected-(U1-(MOSI0{slash}TXD1{slash}OC2A{slash}PTCXY)PB3-Pad15)") (class "Default")
      (node (ref "U1") (pin "15") (pinfunction "(MOSI0/TXD1/OC2A/PTCXY)PB3_15") (pintype "unspecified+no_connect"))
    )
    (net (code "55") (name "unconnected-(U1-(OC0A{slash}PTCXY{slash}AIN0)PD6-Pad10)") (class "Default")
      (node (ref "U1") (pin "10") (pinfunction "(OC0A/PTCXY/AIN0)PD6_10") (pintype "unspecified+no_connect"))
    )
    (net (code "56") (name "unconnected-(U1-(OC0B{slash}T1{slash}PTCXY)PD5-Pad9)") (class "Default")
      (node (ref "U1") (pin "9") (pinfunction "(OC0B/T1/PTCXY)PD5_9") (pintype "unspecified+no_connect"))
    )
    (net (code "57") (name "unconnected-(U1-(OC1A{slash}PTCXY)PB1-Pad13)") (class "Default")
      (node (ref "U1") (pin "13") (pinfunction "(OC1A/PTCXY)PB1_13") (pintype "unspecified+no_connect"))
    )
    (net (code "58") (name "unconnected-(U1-(OC2B{slash}INT1{slash}PTCXY)PD3-Pad1)") (class "Default")
      (node (ref "U1") (pin "1") (pinfunction "(OC2B/INT1/PTCXY)PD3_1") (pintype "unspecified+no_connect"))
    )
    (net (code "59") (name "unconnected-(U1-(PTCXY{slash}AIN1)PD7-Pad11)") (class "Default")
      (node (ref "U1") (pin "11") (pinfunction "(PTCXY/AIN1)PD7_11") (pintype "unspecified+no_connect"))
    )
    (net (code "60") (name "unconnected-(U1-(SS0#{slash}OC1B{slash}PTCXY)PB2-Pad14)") (class "Default")
      (node (ref "U1") (pin "14") (pinfunction "(SS0#/OC1B/PTCXY)PB2_14") (pintype "unspecified+no_connect"))
    )
    (net (code "61") (name "unconnected-(U1-(XCK0{slash}T0{slash}PTCXY)PD4-Pad2)") (class "Default")
      (node (ref "U1") (pin "2") (pinfunction "(XCK0/T0/PTCXY)PD4_2") (pintype "unspecified+no_connect"))
    )
    (net (code "62") (name "unconnected-(U1-AREF-Pad20)") (class "Default")
      (node (ref "U1") (pin "20") (pinfunction "AREF_20") (pintype "unspecified+no_connect"))
    )
    (net (code "63") (name "unconnected-(U1-EP-Pad33)") (class "Default")
      (node (ref "U1") (pin "33") (pinfunction "EP_33") (pintype "unspecified+no_connect"))
    )
    (net (code "64") (name "unconnected-(U1-PB5(PTCXY{slash}XCK1{slash}SCK0)-Pad17)") (class "Default")
      (node (ref "U1") (pin "17") (pinfunction "PB5(PTCXY/XCK1/SCK0)_17") (pintype "unspecified+no_connect"))
    )
    (net (code "65") (name "unconnected-(U1-PC6(RESET#)-Pad29)") (class "Default")
      (node (ref "U1") (pin "29") (pinfunction "PC6(RESET#)_29") (pintype "unspecified+no_connect"))
    )
    (net (code "66") (name "unconnected-(U1-PE2(ADC6{slash}PTCY{slash}ICP3{slash}SS1#)-Pad19)") (class "Default")
      (node (ref "U1") (pin "19") (pinfunction "PE2(ADC6/PTCY/ICP3/SS1#)_19") (pintype "unspecified+no_connect"))
    )
    (net (code "67") (name "unconnected-(U1-PE3(ADC7{slash}PTCY{slash}T3{slash}MOSI1)-Pad22)") (class "Default")
      (node (ref "U1") (pin "22") (pinfunction "PE3(ADC7/PTCY/T3/MOSI1)_22") (pintype "unspecified+no_connect"))
    )
    (net (code "68") (name "unconnected-(U2-EP-Pad9)") (class "Default")
      (node (ref "U2") (pin "9") (pinfunction "EP_9") (pintype "unspecified+no_connect"))
    )
    (net (code "69") (name "unconnected-(U4-NC-Pad8)") (class "Default")
      (node (ref "U4") (pin "8") (pinfunction "NC_8") (pintype "unspecified+no_connect"))
    )
    (net (code "70") (name "unconnected-(U4-OFFSET_N1-Pad1)") (class "Default")
      (node (ref "U4") (pin "1") (pinfunction "OFFSET_N1_1") (pintype "unspecified+no_connect"))
    )
    (net (code "71") (name "unconnected-(U4-OFFSET_N2-Pad5)") (class "Default")
      (node (ref "U4") (pin "5") (pinfunction "OFFSET_N2_5") (pintype "unspecified+no_connect"))
    )
    (net (code "72") (name "unconnected-(U5-GAIN-Pad1)") (class "Default")
      (node (ref "U5") (pin "1") (pinfunction "GAIN_1") (pintype "unspecified+no_connect"))
    )
    (net (code "73") (name "unconnected-(U5-GAIN-Pad8)") (class "Default")
      (node (ref "U5") (pin "8") (pinfunction "GAIN_8") (pintype "unspecified+no_connect"))
    )
    (net (code "74") (name "unconnected-(U9-NC-Pad8)") (class "Default")
      (node (ref "U9") (pin "8") (pinfunction "NC_8") (pintype "unspecified+no_connect"))
    )
    (net (code "75") (name "unconnected-(U9-OFFSET_N1-Pad1)") (class "Default")
      (node (ref "U9") (pin "1") (pinfunction "OFFSET_N1_1") (pintype "unspecified+no_connect"))
    )
    (net (code "76") (name "unconnected-(U9-OFFSET_N2-Pad5)") (class "Default")
      (node (ref "U9") (pin "5") (pinfunction "OFFSET_N2_5") (pintype "unspecified+no_connect"))
    )
    (net (code "77") (name "unconnected-(USB1-EH-Pad25)") (class "Default")
      (node (ref "USB1") (pin "25") (pinfunction "EH_25") (pintype "unspecified+no_connect"))
    )
    (net (code "78") (name "unconnected-(USB1-EH-Pad26)") (class "Default")
      (node (ref "USB1") (pin "26") (pinfunction "EH_26") (pintype "unspecified+no_connect"))
    )
    (net (code "79") (name "unconnected-(USB1-EH-Pad27)") (class "Default")
      (node (ref "USB1") (pin "27") (pinfunction "EH_27") (pintype "unspecified+no_connect"))
    )
    (net (code "80") (name "unconnected-(USB1-EH-Pad28)") (class "Default")
      (node (ref "USB1") (pin "28") (pinfunction "EH_28") (pintype "unspecified+no_connect"))
    )
    (net (code "81") (name "unconnected-(USB1-EH-Pad29)") (class "Default")
      (node (ref "USB1") (pin "29") (pinfunction "EH_29") (pintype "unspecified+no_connect"))
    )
    (net (code "82") (name "unconnected-(USB1-EH-Pad30)") (class "Default")
      (node (ref "USB1") (pin "30") (pinfunction "EH_30") (pintype "unspecified+no_connect"))
    )
    (net (code "83") (name "unconnected-(USB1-SSRXn1-PadB10)") (class "Default")
      (node (ref "USB1") (pin "B10") (pinfunction "SSRXn1_B10") (pintype "unspecified+no_connect"))
    )
    (net (code "84") (name "unconnected-(USB1-SSRXn2-PadA10)") (class "Default")
      (node (ref "USB1") (pin "A10") (pinfunction "SSRXn2_A10") (pintype "unspecified+no_connect"))
    )
    (net (code "85") (name "unconnected-(USB1-SSRXp1-PadB11)") (class "Default")
      (node (ref "USB1") (pin "B11") (pinfunction "SSRXp1_B11") (pintype "unspecified+no_connect"))
    )
    (net (code "86") (name "unconnected-(USB1-SSRXp2-PadA11)") (class "Default")
      (node (ref "USB1") (pin "A11") (pinfunction "SSRXp2_A11") (pintype "unspecified+no_connect"))
    )
    (net (code "87") (name "unconnected-(USB1-SSTXn1-PadA3)") (class "Default")
      (node (ref "USB1") (pin "A3") (pinfunction "SSTXn1_A3") (pintype "unspecified+no_connect"))
    )
    (net (code "88") (name "unconnected-(USB1-SSTXn2-PadB3)") (class "Default")
      (node (ref "USB1") (pin "B3") (pinfunction "SSTXn2_B3") (pintype "unspecified+no_connect"))
    )
    (net (code "89") (name "unconnected-(USB1-SSTXp1-PadA2)") (class "Default")
      (node (ref "USB1") (pin "A2") (pinfunction "SSTXp1_A2") (pintype "unspecified+no_connect"))
    )
    (net (code "90") (name "unconnected-(USB1-SSTXp2-PadB2)") (class "Default")
      (node (ref "USB1") (pin "B2") (pinfunction "SSTXp2_B2") (pintype "unspecified+no_connect"))
    )
    (net (code "91") (name "unconnected-(USB1-SUB1-PadA8)") (class "Default")
      (node (ref "USB1") (pin "A8") (pinfunction "SUB1_A8") (pintype "unspecified+no_connect"))
    )
    (net (code "92") (name "unconnected-(USB1-SUB2-PadB8)") (class "Default")
      (node (ref "USB1") (pin "B8") (pinfunction "SUB2_B8") (pintype "unspecified+no_connect"))
    )
  )
)
